# PWR_P5V0.net
KiCad netlist of a schematic drawn in Altium Designer
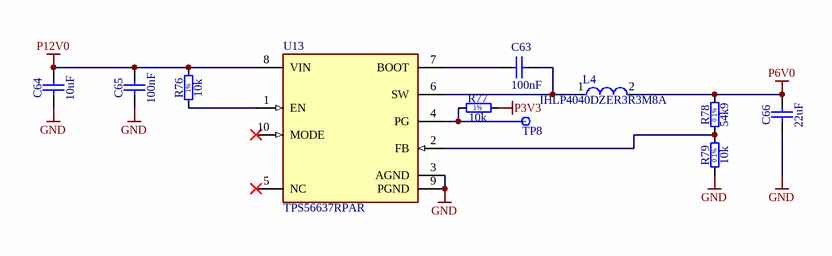
[diagram p0: PWR_P5V0.SchDoc]

(export (version "E")
  (design (tool "Eeschema 10.0.6"))
  (components
    (comp (ref "C63")
      (value "100nF")
      (footprint "CAPC1005X55N")
      (description "Non-polarised capacitor")
      (fields
        (field (name "PART NUMBER") "CC0402_100NF_16V_10%_X5R")
        (field (name "VOLTAGE") "16V")
        (field (name "AUTHOR") "CERN DEM JLC")
      )
      (libsource (lib "Capacitors") (part "Capacitor - non polarized"))
    )
    (comp (ref "C64")
      (value "10uF")
      (footprint "CAPC2012X95N")
      (description "Non-polarised capacitor")
      (fields
        (field (name "PART NUMBER") "CC0805_10UF_25V_10%_X5R")
        (field (name "VOLTAGE") "25V")
        (field (name "AUTHOR") "CERN DEM JLC")
      )
      (libsource (lib "Capacitors") (part "Capacitor - non polarized"))
    )
    (comp (ref "C65")
      (value "100nF")
      (footprint "CAPC1005X55N")
      (description "Non-polarised capacitor")
      (fields
        (field (name "PART NUMBER") "CC0402_100NF_16V_10%_X5R")
        (field (name "VOLTAGE") "16V")
        (field (name "AUTHOR") "CERN DEM JLC")
      )
      (libsource (lib "Capacitors") (part "Capacitor - non polarized"))
    )
    (comp (ref "C66")
      (value "22uF")
      (footprint "CAPC2012X135N")
      (description "Non-polarised capacitor")
      (fields
        (field (name "PART NUMBER") "CC0805_22UF_16V_10%_X5R")
        (field (name "VOLTAGE") "16V")
        (field (name "AUTHOR") "CERN DEM JLC")
      )
      (libsource (lib "Capacitors") (part "Capacitor - non polarized"))
    )
    (comp (ref "L4")
      (value "IHLP4040DZER3R3M8A")
      (footprint "FP-IHLP4040DZER3R3M8A-MFG")
      (description "FIXED IND 3.3UH 11A 11.81 MOHM")
      (fields
        (field (name "MANUFACTURER") "Vishay")
        (field (name "OCTOPART") "https://octopart.com/ihlp4040dzer3r3m8a-vishay-52741166")
      )
      (libsource (lib "Altium Content Vault") (part "725321dda6339637d4d059423bc1c3c"))
    )
    (comp (ref "R76")
      (value "10k")
      (footprint "RESC1005X40N")
      (description "Resistor - 1%")
      (fields
        (field (name "PART NUMBER") "R0402_10K_1%_0.0625W_100PPM")
        (field (name "MANUFACTURER") "GENERIC")
        (field (name "AUTHOR") "CERN DEM JLC")
      )
      (libsource (lib "Resistors") (part "Resistor - 1%"))
    )
    (comp (ref "R77")
      (value "10k")
      (footprint "RESC1005X40N")
      (description "Resistor - 1%")
      (fields
        (field (name "PART NUMBER") "R0402_10K_1%_0.0625W_100PPM")
        (field (name "MANUFACTURER") "GENERIC")
        (field (name "AUTHOR") "CERN DEM JLC")
      )
      (libsource (lib "Resistors") (part "Resistor - 1%"))
    )
    (comp (ref "R78")
      (value "54k9")
      (footprint "RESC1608X55N")
      (description "Resistor - 0.1%")
      (fields
        (field (name "PART NUMBER") "R0603_54K9_0.1%_0.063W_10PPM")
        (field (name "MANUFACTURER") "GENERIC")
        (field (name "AUTHOR") "CERN DEM JLC")
      )
      (libsource (lib "Resistors") (part "Resistor - 0.1%"))
    )
    (comp (ref "R79")
      (value "10k")
      (footprint "RESC1608X55N")
      (description "Resistor - 0.1%")
      (fields
        (field (name "PART NUMBER") "R0603_10K_0.1%_0.063W_10PPM")
        (field (name "MANUFACTURER") "GENERIC")
        (field (name "AUTHOR") "CERN DEM JLC")
      )
      (libsource (lib "Resistors") (part "Resistor - 0.1%"))
    )
    (comp (ref "TP8")
      (value "Test Point")
      (footprint "TPS127")
      (fields (field (name "PART NUMBER") "SMD_PAD_1.27X1.27MM") (field (name "AUTHOR") "CERN DEM JLC"))
      (libsource (lib "Eletro-mechanical") (part "Test Point"))
    )
    (comp (ref "U13")
      (value "TPS56637RPAR")
      (footprint "FP-RPA0010A-MFG")
      (description "IC POWER MANAGEMENT")
      (fields
        (field (name "OCTOPART") "https://octopart.com/tps56637rpar-texas+instruments-97650653")
        (field (name "MANUFACTURER") "Texas Instruments")
      )
      (libsource (lib "Altium Content Vault") (part "31007e10bcfaaa9b7385bfd54c3e755"))
    )
  )
  (nets
    (net (code "1") (name "GND") (class "Default")
      (node (ref "C64") (pin "1") (pinfunction "1_1") (pintype "passive"))
      (node (ref "C65") (pin "1") (pinfunction "1_1") (pintype "passive"))
      (node (ref "C66") (pin "1") (pinfunction "1_1") (pintype "passive"))
      (node (ref "R79") (pin "1") (pinfunction "1_1") (pintype "passive"))
      (node (ref "U13") (pin "3") (pinfunction "AGND_3") (pintype "power_in"))
      (node (ref "U13") (pin "9") (pinfunction "PGND_9") (pintype "power_in"))
    )
    (net (code "2") (name "Net-(U13-BOOT)") (class "Default")
      (node (ref "C63") (pin "2") (pinfunction "2_2") (pintype "passive"))
      (node (ref "U13") (pin "7") (pinfunction "BOOT_7") (pintype "power_in"))
    )
    (net (code "3") (name "Net-(U13-EN)") (class "Default")
      (node (ref "R76") (pin "1") (pinfunction "1_1") (pintype "passive"))
      (node (ref "U13") (pin "1") (pinfunction "EN_1") (pintype "input"))
    )
    (net (code "4") (name "Net-(U13-FB)") (class "Default")
      (node (ref "R78") (pin "1") (pinfunction "1_1") (pintype "passive"))
      (node (ref "R79") (pin "2") (pinfunction "2_2") (pintype "passive"))
      (node (ref "U13") (pin "2") (pinfunction "FB_2") (pintype "input"))
    )
    (net (code "5") (name "Net-(U13-PG)") (class "Default")
      (node (ref "R77") (pin "1") (pinfunction "1_1") (pintype "passive"))
      (node (ref "TP8") (pin "1") (pinfunction "1_1") (pintype "bidirectional"))
      (node (ref "U13") (pin "4") (pinfunction "PG_4") (pintype "open_collector"))
    )
    (net (code "6") (name "Net-(U13-SW)") (class "Default")
      (node (ref "C63") (pin "1") (pinfunction "1_1") (pintype "passive"))
      (node (ref "L4") (pin "1") (pinfunction "1_1") (pintype "passive"))
      (node (ref "U13") (pin "6") (pinfunction "SW_6") (pintype "power_in"))
    )
    (net (code "7") (name "P3V3") (class "Default")
      (node (ref "R77") (pin "2") (pinfunction "2_2") (pintype "passive"))
    )
    (net (code "8") (name "P6V0") (class "Default")
      (node (ref "C66") (pin "2") (pinfunction "2_2") (pintype "passive"))
      (node (ref "L4") (pin "2") (pinfunction "2_2") (pintype "passive"))
      (node (ref "R78") (pin "2") (pinfunction "2_2") (pintype "passive"))
    )
    (net (code "9") (name "P12V0") (class "Default")
      (node (ref "C64") (pin "2") (pinfunction "2_2") (pintype "passive"))
      (node (ref "C65") (pin "2") (pinfunction "2_2") (pintype "passive"))
      (node (ref "R76") (pin "2") (pinfunction "2_2") (pintype "passive"))
      (node (ref "U13") (pin "8") (pinfunction "VIN_8") (pintype "power_in"))
    )
    (net (code "10") (name "unconnected-(U13-MODE-Pad10)") (class "Default")
      (node (ref "U13") (pin "10") (pinfunction "MODE_10") (pintype "input+no_connect"))
    )
    (net (code "11") (name "unconnected-(U13-NC-Pad5)") (class "Default")
      (node (ref "U13") (pin "5") (pinfunction "NC_5") (pintype "passive+no_connect"))
    )
  )
)
